# Power_Switch.net
KiCad netlist of a schematic drawn in Altium Designer
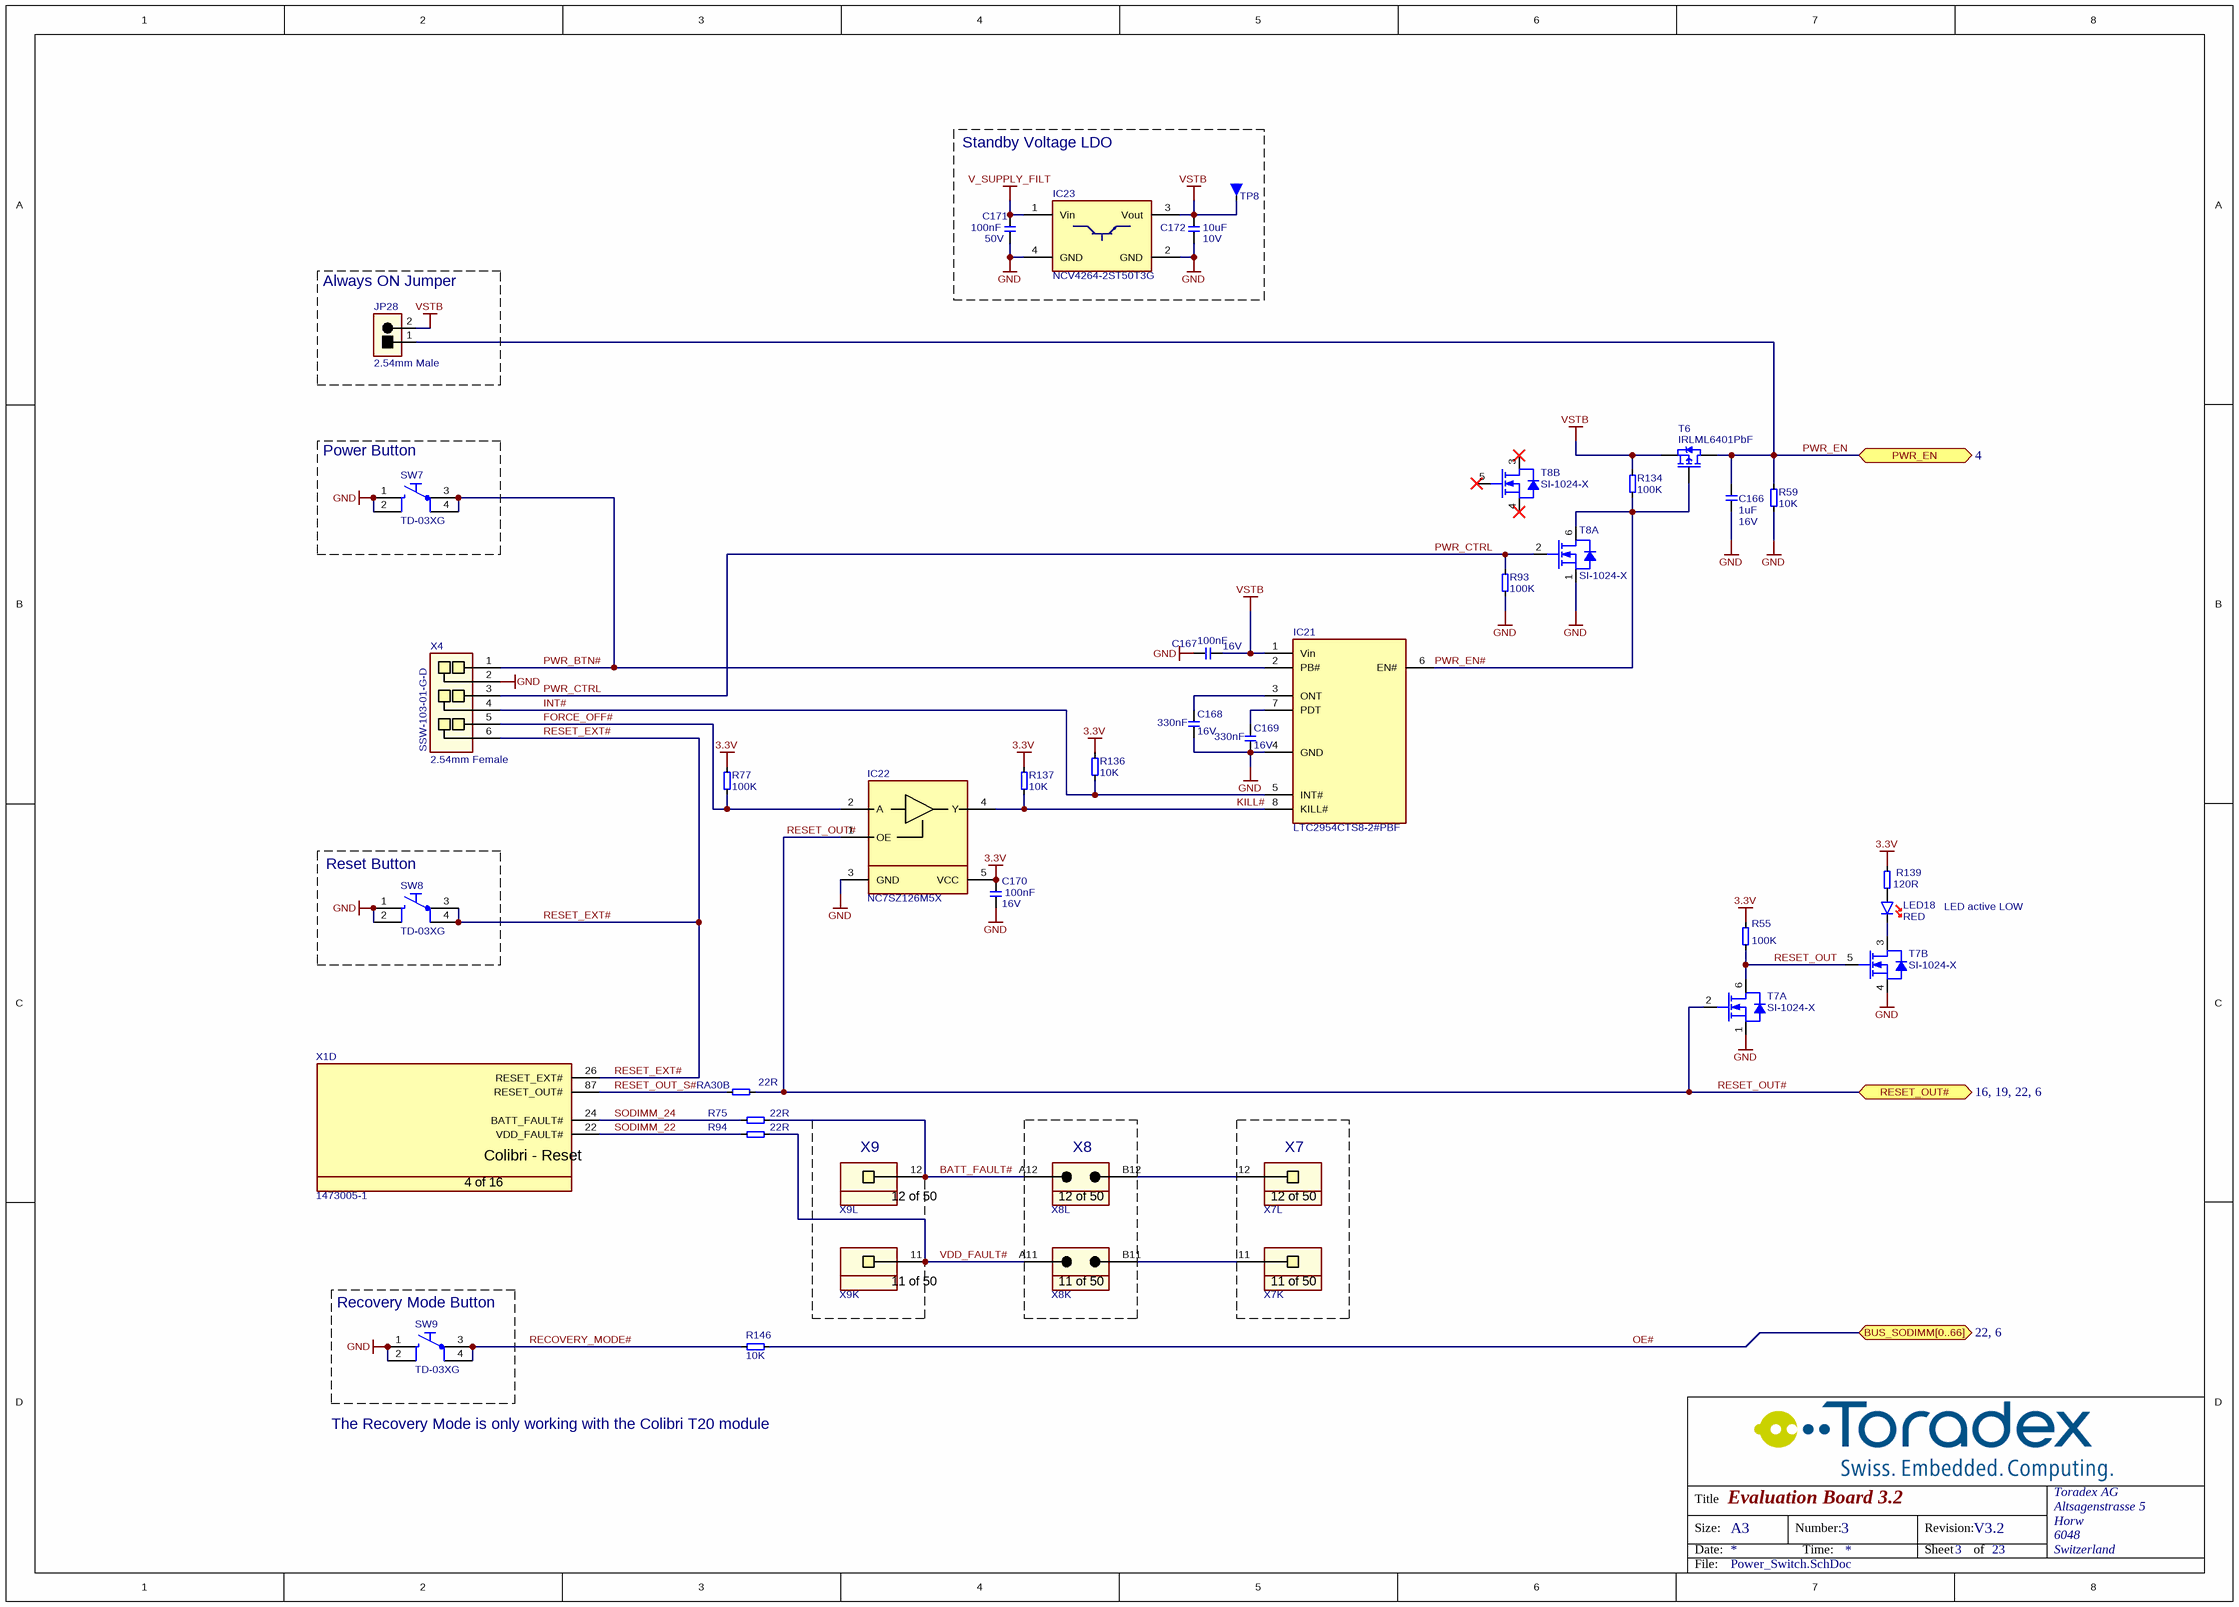
[diagram p0: Power_Switch.SchDoc]

(export (version "E")
  (design (tool "Eeschema 10.0.6"))
  (components
    (comp (ref "C166")
      (value "1uF")
      (footprint "T_CAPC0603X33N")
      (description "Capacitor Ceramic X5R 1uF 16V 20% 0603")
      (fields (field (name "TOLERANCE") "20%") (field (name "RATING") "16V"))
      (libsource (lib "Evaluation Board") (part "C-X5R-1uF-16V-20%-0603"))
    )
    (comp (ref "C167")
      (value "100nF")
      (footprint "T_CAPC0603X33N")
      (description "Capacitor Ceramic X7R 100nF 16V 10% 0603")
      (fields (field (name "TOLERANCE") "10%") (field (name "RATING") "16V"))
      (libsource (lib "Evaluation Board") (part "C-X7R-100nF-16V-10%-0603"))
    )
    (comp (ref "C168")
      (value "330nF")
      (footprint "T_CAPC0805X125N")
      (description "Capacitor Ceramic X7R 330nF 16V 10% 0805")
      (fields (field (name "TOLERANCE") "10%") (field (name "RATING") "16V"))
      (libsource (lib "Evaluation Board") (part "C-X7R-330nF-16V-10%-0805"))
    )
    (comp (ref "C169")
      (value "330nF")
      (footprint "T_CAPC0805X125N")
      (description "Capacitor Ceramic X7R 330nF 16V 10% 0805")
      (fields (field (name "TOLERANCE") "10%") (field (name "RATING") "16V"))
      (libsource (lib "Evaluation Board") (part "C-X7R-330nF-16V-10%-0805"))
    )
    (comp (ref "C170")
      (value "100nF")
      (footprint "T_CAPC0603X33N")
      (description "Capacitor Ceramic X7R 100nF 16V 10% 0603")
      (fields (field (name "TOLERANCE") "10%") (field (name "RATING") "16V"))
      (libsource (lib "Evaluation Board") (part "C-X7R-100nF-16V-10%-0603"))
    )
    (comp (ref "C171")
      (value "100nF")
      (footprint "T_CAPC0603X33N")
      (description "Capacitor Ceramic X7R 100nF 50V 20% 0603")
      (fields (field (name "TOLERANCE") "20%") (field (name "RATING") "50V"))
      (libsource (lib "Evaluation Board") (part "C-X7R-100nF-50V-20%-0603"))
    )
    (comp (ref "C172")
      (value "10uF")
      (footprint "T_CAPC0805X125N")
      (description "Capacitor Ceramic X5R 10uF 10V 20% 0805")
      (fields (field (name "TOLERANCE") "20%") (field (name "RATING") "10V"))
      (libsource (lib "Evaluation Board") (part "C-X5R-10uF-10V-20%-0805"))
    )
    (comp (ref "IC21")
      (value "LTC2954CTS8-2#PBF")
      (footprint "T_LINEAR_LTC2954CTS8-2#PBF")
      (description "Push Button On/Off Controller")
      (fields (field (name "MANUFACTURER PART NO.") "LTC2954CTS8-2#PBF"))
      (libsource (lib "Evaluation Board") (part "IC-LIN-LTC2954CTS8-2#PBF"))
    )
    (comp (ref "IC22")
      (value "NC7SZ126M5X")
      (footprint "SOT95P279X142-5N")
      (description "NC7SZ126M5X  Buffer Three-State Output")
      (fields (field (name "MANUFACTURER PART NO.") "NC7SZ126M5X"))
      (libsource (lib "Evaluation Board") (part "IC-FAR-NC7SZ126M5X"))
    )
    (comp (ref "IC23")
      (value "NCV4264-2ST50T3G")
      (footprint "T_ON_NCV4264-2ST50T3G")
      (description "NCV4264-2ST50T3G LDO Regulator")
      (fields (field (name "MANUFACTURER PART NO.") "NCV4264-2ST50T3G"))
      (libsource (lib "Evaluation Board") (part "IC-ON-NCV4264-2ST50T3G"))
    )
    (comp (ref "JP28")
      (value "TSW-101-07-G-D")
      (footprint "T_Samtec_TSW-101-07-G-D")
      (description "Header male, 1x2 Pins, 2.54 mm pitch")
      (libsource (lib "Evaluation Board") (part "CON-Samtec-TSW-101-07-G-D"))
    )
    (comp (ref "LED18")
      (value "LS T670-K1L2-1")
      (footprint "T_Osram_T670_RED")
      (description "LED red, Osram LS T670-K1L2-1")
      (fields (field (name "COLOR") "RED"))
      (libsource (lib "Evaluation Board") (part "LED-Osram-LS T670-K1L2-1"))
    )
    (comp (ref "R55")
      (value "100K")
      (footprint "T_RESC0603X30N")
      (description "Resistor 100 Kohm 63mW 5% 0603")
      (fields (field (name "TOLERANCE") "5%"))
      (libsource (lib "Evaluation Board") (part "R-100KR-63mW-5%-0603"))
    )
    (comp (ref "R59")
      (value "10K")
      (footprint "T_RESC0603X30N")
      (description "Resistor 10 Kohm 63mW 5% 0603")
      (fields (field (name "TOLERANCE") "5%"))
      (libsource (lib "Evaluation Board") (part "R-10KR-63mW-5%-0603"))
    )
    (comp (ref "R75")
      (value "22R")
      (footprint "RESC1005X40N")
      (description "Resistor 22 ohm 63mW 5% 0402")
      (fields (field (name "TOLERANCE") "5%"))
      (libsource (lib "Evaluation Board") (part "R-22R-63mW-5%-0402"))
    )
    (comp (ref "R77")
      (value "100K")
      (footprint "T_RESC0603X30N")
      (description "Resistor 100 Kohm 63mW 5% 0603")
      (fields (field (name "TOLERANCE") "5%"))
      (libsource (lib "Evaluation Board") (part "R-100KR-63mW-5%-0603"))
    )
    (comp (ref "R93")
      (value "100K")
      (footprint "T_RESC0603X30N")
      (description "Resistor 100 Kohm 63mW 5% 0603")
      (fields (field (name "TOLERANCE") "5%"))
      (libsource (lib "Evaluation Board") (part "R-100KR-63mW-5%-0603"))
    )
    (comp (ref "R94")
      (value "22R")
      (footprint "RESC1005X40N")
      (description "Resistor 22 ohm 63mW 5% 0402")
      (fields (field (name "TOLERANCE") "5%"))
      (libsource (lib "Evaluation Board") (part "R-22R-63mW-5%-0402"))
    )
    (comp (ref "R134")
      (value "100K")
      (footprint "T_RESC0603X30N")
      (description "Resistor 100 Kohm 63mW 5% 0603")
      (fields (field (name "TOLERANCE") "5%"))
      (libsource (lib "Evaluation Board") (part "R-100KR-63mW-5%-0603"))
    )
    (comp (ref "R136")
      (value "10K")
      (footprint "T_RESC0603X30N")
      (description "Resistor 10 Kohm 63mW 5% 0603")
      (fields (field (name "TOLERANCE") "5%"))
      (libsource (lib "Evaluation Board") (part "R-10KR-63mW-5%-0603"))
    )
    (comp (ref "R137")
      (value "10K")
      (footprint "T_RESC0603X30N")
      (description "Resistor 10 Kohm 63mW 5% 0603")
      (fields (field (name "TOLERANCE") "5%"))
      (libsource (lib "Evaluation Board") (part "R-10KR-63mW-5%-0603"))
    )
    (comp (ref "R139")
      (value "120R")
      (footprint "T_RESC0603X30N")
      (description "Resistor 120 ohm 63mW 5% 0603")
      (fields (field (name "TOLERANCE") "5%"))
      (libsource (lib "Evaluation Board") (part "R-120R-63mW-5%-0603"))
    )
    (comp (ref "R146")
      (value "10K")
      (footprint "T_RESC0603X30N")
      (description "Resistor 10 Kohm 63mW 5% 0603")
      (fields (field (name "TOLERANCE") "5%"))
      (libsource (lib "Evaluation Board") (part "R-10KR-63mW-5%-0603"))
    )
    (comp (ref "RA30")
      (value "22R")
      (footprint "T_Resistor_Array_X4")
      (description "Resistor Array 22 R 63mW 5% 1206")
      (fields (field (name "TOLERANCE") "5%"))
      (libsource (lib "Evaluation Board") (part "RA-22R-63mW-5%-1206-div"))
    )
    (comp (ref "SW7")
      (value "TD-03XG")
      (footprint "T_WMF_TD-03XG")
      (description "Switch")
      (libsource (lib "Evaluation Board") (part "SW-WMF-TD-03XG"))
    )
    (comp (ref "SW8")
      (value "TD-03XG")
      (footprint "T_WMF_TD-03XG")
      (description "Switch")
      (libsource (lib "Evaluation Board") (part "SW-WMF-TD-03XG"))
    )
    (comp (ref "SW9")
      (value "TD-03XG")
      (footprint "T_WMF_TD-03XG")
      (description "Switch")
      (libsource (lib "Evaluation Board") (part "SW-WMF-TD-03XG"))
    )
    (comp (ref "T6")
      (value "IRLML6401PbF")
      (footprint "SOT95P237X112-3N")
      (description "p-channel MOSFET, IRLML6401PbF")
      (libsource (lib "Evaluation Board") (part "T-IR-IRLML6401PbF-SOT-23"))
    )
    (comp (ref "T7")
      (value "T-Vishay-SI-1024X-N")
      (footprint "SOTFL50P160X60-6N")
      (description "Dual N-Channel 20V (D-S)  MOSFET")
      (fields (field (name "MANUFACTURER PART NO.") "SI-1024-X"))
      (libsource (lib "Evaluation Board") (part "T-Vishay-SI-1024X-N"))
    )
    (comp (ref "T8")
      (value "T-Vishay-SI-1024X-N")
      (footprint "SOTFL50P160X60-6N")
      (description "Dual N-Channel 20V (D-S)  MOSFET")
      (fields (field (name "MANUFACTURER PART NO.") "SI-1024-X"))
      (libsource (lib "Evaluation Board") (part "T-Vishay-SI-1024X-N"))
    )
    (comp (ref "TP8")
      (value "Testpin")
      (footprint "T_TP-THT")
      (description "Testpin TH")
      (libsource (lib "Evaluation Board") (part "Testpin"))
    )
    (comp (ref "X1")
      (value "CON-Tyco-1473005-1-200-0.6mm")
      (footprint "T_Tyco_1473005-1")
      (description "SODIMM Connector")
      (fields (field (name "MANUFACTURER PART NO.") "1473005-1"))
      (libsource (lib "Evaluation Board") (part "CON-Tyco-1473005-1-200-0.6mm"))
    )
    (comp (ref "X4")
      (value "TSW-103-01-G-D")
      (footprint "T_Samtec_SSW-103-01-G-D")
      (description "Header Female, 2x3 Pins, 2.54mm pitch")
      (fields (field (name "MANUFACTURER PART NO.") "SSW-103-01-G-D"))
      (libsource (lib "Evaluation Board") (part "CON-Samtec-SSW-103-01-G-D"))
    )
    (comp (ref "X7")
      (value "SSW-110-01-G-S")
      (footprint "T_Samtec_SSW-110-01-G-S")
      (description "Header 1x50 pin 2.54mm pitch")
      (libsource (lib "Evaluation Board") (part "CON-Samtec-SSW-110-01-G-S"))
    )
    (comp (ref "X8")
      (value "TSW-110-07-G-D")
      (footprint "T_Samtec_TSW-110-07-G-D")
      (description "Header 2x50 pin 2.54mm pitch")
      (libsource (lib "Evaluation Board") (part "CON-Samtec-TSW-110-07-G-D"))
    )
    (comp (ref "X9")
      (value "SSW-110-01-G-S")
      (footprint "T_Samtec_SSW-110-01-G-S")
      (description "Header 1x50 pin 2.54mm pitch")
      (libsource (lib "") (part "CON-Samtec-SSW-110-01-G-S_1"))
    )
  )
  (nets
    (net (code "68") (name "/BATT_FAULT#") (class "Default")
      (node (ref "R75") (pin "2") (pinfunction "2_2") (pintype "passive"))
      (node (ref "X8") (pin "A12") (pinfunction "A12_A12") (pintype "passive"))
      (node (ref "X9") (pin "12") (pinfunction "12_12") (pintype "passive"))
    )
    (net (code "70") (name "/FORCE_OFF#") (class "Default")
      (node (ref "IC22") (pin "2") (pinfunction "A_2") (pintype "passive"))
      (node (ref "R77") (pin "1") (pinfunction "1_1") (pintype "passive"))
      (node (ref "X4") (pin "5") (pinfunction "5_5") (pintype "passive"))
    )
    (net (code "71") (name "/INT#") (class "Default")
      (node (ref "IC21") (pin "5") (pinfunction "INT#_5") (pintype "passive"))
      (node (ref "R136") (pin "2") (pinfunction "2_2") (pintype "passive"))
      (node (ref "X4") (pin "4") (pinfunction "4_4") (pintype "passive"))
    )
    (net (code "72") (name "/KILL#") (class "Default")
      (node (ref "IC21") (pin "8") (pinfunction "KILL#_8") (pintype "passive"))
      (node (ref "IC22") (pin "4") (pinfunction "Y_4") (pintype "passive"))
      (node (ref "R137") (pin "2") (pinfunction "2_2") (pintype "passive"))
    )
    (net (code "73") (name "/OE#") (class "Default")
      (node (ref "R146") (pin "2") (pinfunction "2_2") (pintype "passive"))
    )
    (net (code "74") (name "/PWR_BTN#") (class "Default")
      (node (ref "IC21") (pin "2") (pinfunction "PB#_2") (pintype "passive"))
      (node (ref "SW7") (pin "3") (pinfunction "3_3") (pintype "passive"))
      (node (ref "SW7") (pin "4") (pinfunction "4_4") (pintype "passive"))
      (node (ref "X4") (pin "1") (pinfunction "1_1") (pintype "passive"))
    )
    (net (code "75") (name "/PWR_CTRL") (class "Default")
      (node (ref "R93") (pin "2") (pinfunction "2_2") (pintype "passive"))
      (node (ref "T8") (pin "2") (pinfunction "G_2") (pintype "passive"))
      (node (ref "X4") (pin "3") (pinfunction "3_3") (pintype "passive"))
    )
    (net (code "76") (name "/PWR_EN") (class "Default")
      (node (ref "C166") (pin "2") (pinfunction "2_2") (pintype "passive"))
      (node (ref "JP28") (pin "1") (pinfunction "1_1") (pintype "passive"))
      (node (ref "R59") (pin "2") (pinfunction "2_2") (pintype "passive"))
      (node (ref "T6") (pin "3") (pinfunction "3_3") (pintype "passive"))
    )
    (net (code "77") (name "/PWR_EN#") (class "Default")
      (node (ref "IC21") (pin "6") (pinfunction "EN#_6") (pintype "passive"))
      (node (ref "R134") (pin "1") (pinfunction "1_1") (pintype "passive"))
      (node (ref "T6") (pin "1") (pinfunction "1_1") (pintype "passive"))
      (node (ref "T8") (pin "6") (pinfunction "D_6") (pintype "passive"))
    )
    (net (code "78") (name "/RECOVERY_MODE#") (class "Default")
      (node (ref "R146") (pin "1") (pinfunction "1_1") (pintype "passive"))
      (node (ref "SW9") (pin "3") (pinfunction "3_3") (pintype "passive"))
      (node (ref "SW9") (pin "4") (pinfunction "4_4") (pintype "passive"))
    )
    (net (code "79") (name "/RESET_EXT#") (class "Default")
      (node (ref "SW8") (pin "3") (pinfunction "3_3") (pintype "passive"))
      (node (ref "SW8") (pin "4") (pinfunction "4_4") (pintype "passive"))
      (node (ref "X1") (pin "26") (pinfunction "RESET_EXT#_26") (pintype "passive"))
      (node (ref "X4") (pin "6") (pinfunction "6_6") (pintype "passive"))
    )
    (net (code "80") (name "/RESET_OUT") (class "Default")
      (node (ref "R55") (pin "1") (pinfunction "1_1") (pintype "passive"))
      (node (ref "T7") (pin "5") (pinfunction "G_5") (pintype "passive"))
      (node (ref "T7") (pin "6") (pinfunction "D_6") (pintype "passive"))
    )
    (net (code "81") (name "/RESET_OUT#") (class "Default")
      (node (ref "IC22") (pin "1") (pinfunction "OE_1") (pintype "passive"))
      (node (ref "RA30") (pin "6") (pinfunction "6_6") (pintype "passive"))
      (node (ref "T7") (pin "2") (pinfunction "G_2") (pintype "passive"))
    )
    (net (code "82") (name "/RESET_OUT_S#") (class "Default")
      (node (ref "RA30") (pin "2") (pinfunction "2_2") (pintype "passive"))
      (node (ref "X1") (pin "87") (pinfunction "RESET_OUT#_87") (pintype "passive"))
    )
    (net (code "83") (name "/SODIMM_22") (class "Default")
      (node (ref "R94") (pin "1") (pinfunction "1_1") (pintype "passive"))
      (node (ref "X1") (pin "22") (pinfunction "VDD_FAULT#_22") (pintype "passive"))
    )
    (net (code "84") (name "/SODIMM_24") (class "Default")
      (node (ref "R75") (pin "1") (pinfunction "1_1") (pintype "passive"))
      (node (ref "X1") (pin "24") (pinfunction "BATT_FAULT#_24") (pintype "passive"))
    )
    (net (code "85") (name "/VDD_FAULT#") (class "Default")
      (node (ref "R94") (pin "2") (pinfunction "2_2") (pintype "passive"))
      (node (ref "X8") (pin "A11") (pinfunction "A11_A11") (pintype "passive"))
      (node (ref "X9") (pin "11") (pinfunction "11_11") (pintype "passive"))
    )
    (net (code "86") (name "3.3V") (class "Default")
      (node (ref "C170") (pin "1") (pinfunction "1_1") (pintype "passive"))
      (node (ref "IC22") (pin "5") (pinfunction "VCC_5") (pintype "passive"))
      (node (ref "R136") (pin "1") (pinfunction "1_1") (pintype "passive"))
      (node (ref "R137") (pin "1") (pinfunction "1_1") (pintype "passive"))
      (node (ref "R139") (pin "2") (pinfunction "2_2") (pintype "passive"))
      (node (ref "R55") (pin "2") (pinfunction "2_2") (pintype "passive"))
      (node (ref "R77") (pin "2") (pinfunction "2_2") (pintype "passive"))
    )
    (net (code "87") (name "GND") (class "Default")
      (node (ref "C166") (pin "1") (pinfunction "1_1") (pintype "passive"))
      (node (ref "C167") (pin "1") (pinfunction "1_1") (pintype "passive"))
      (node (ref "C168") (pin "1") (pinfunction "1_1") (pintype "passive"))
      (node (ref "C169") (pin "1") (pinfunction "1_1") (pintype "passive"))
      (node (ref "C170") (pin "2") (pinfunction "2_2") (pintype "passive"))
      (node (ref "C171") (pin "1") (pinfunction "1_1") (pintype "passive"))
      (node (ref "C172") (pin "1") (pinfunction "1_1") (pintype "passive"))
      (node (ref "IC21") (pin "4") (pinfunction "GND_4") (pintype "passive"))
      (node (ref "IC22") (pin "3") (pinfunction "GND_3") (pintype "passive"))
      (node (ref "IC23") (pin "2") (pinfunction "GND_2") (pintype "passive"))
      (node (ref "IC23") (pin "4") (pinfunction "GND_4") (pintype "passive"))
      (node (ref "R59") (pin "1") (pinfunction "1_1") (pintype "passive"))
      (node (ref "R93") (pin "1") (pinfunction "1_1") (pintype "passive"))
      (node (ref "SW7") (pin "1") (pinfunction "1_1") (pintype "passive"))
      (node (ref "SW7") (pin "2") (pinfunction "2_2") (pintype "passive"))
      (node (ref "SW8") (pin "1") (pinfunction "1_1") (pintype "passive"))
      (node (ref "SW8") (pin "2") (pinfunction "2_2") (pintype "passive"))
      (node (ref "SW9") (pin "1") (pinfunction "1_1") (pintype "passive"))
      (node (ref "SW9") (pin "2") (pinfunction "2_2") (pintype "passive"))
      (node (ref "T7") (pin "1") (pinfunction "S_1") (pintype "passive"))
      (node (ref "T7") (pin "4") (pinfunction "S_4") (pintype "passive"))
      (node (ref "T8") (pin "1") (pinfunction "S_1") (pintype "passive"))
      (node (ref "X4") (pin "2") (pinfunction "2_2") (pintype "passive"))
    )
    (net (code "88") (name "Net-(IC21-ONT)") (class "Default")
      (node (ref "C168") (pin "2") (pinfunction "2_2") (pintype "passive"))
      (node (ref "IC21") (pin "3") (pinfunction "ONT_3") (pintype "passive"))
    )
    (net (code "89") (name "Net-(IC21-PDT)") (class "Default")
      (node (ref "C169") (pin "2") (pinfunction "2_2") (pintype "passive"))
      (node (ref "IC21") (pin "7") (pinfunction "PDT_7") (pintype "passive"))
    )
    (net (code "90") (name "Net-(LED18-PadA)") (class "Default")
      (node (ref "LED18") (pin "A") (pinfunction "A_A") (pintype "passive"))
      (node (ref "R139") (pin "1") (pinfunction "1_1") (pintype "passive"))
    )
    (net (code "91") (name "Net-(T7B-D)") (class "Default")
      (node (ref "LED18") (pin "K") (pinfunction "K_K") (pintype "passive"))
      (node (ref "T7") (pin "3") (pinfunction "D_3") (pintype "passive"))
    )
    (net (code "92") (name "Net-(X7-Pad11)") (class "Default")
      (node (ref "X7") (pin "11") (pinfunction "11_11") (pintype "passive"))
      (node (ref "X8") (pin "B11") (pinfunction "B11_B11") (pintype "passive"))
    )
    (net (code "93") (name "Net-(X7-Pad12)") (class "Default")
      (node (ref "X7") (pin "12") (pinfunction "12_12") (pintype "passive"))
      (node (ref "X8") (pin "B12") (pinfunction "B12_B12") (pintype "passive"))
    )
    (net (code "94") (name "VSTB") (class "Default")
      (node (ref "C167") (pin "2") (pinfunction "2_2") (pintype "passive"))
      (node (ref "C172") (pin "2") (pinfunction "2_2") (pintype "passive"))
      (node (ref "IC21") (pin "1") (pinfunction "Vin_1") (pintype "passive"))
      (node (ref "IC23") (pin "3") (pinfunction "Vout_3") (pintype "passive"))
      (node (ref "JP28") (pin "2") (pinfunction "2_2") (pintype "passive"))
      (node (ref "R134") (pin "2") (pinfunction "2_2") (pintype "passive"))
      (node (ref "T6") (pin "2") (pinfunction "2_2") (pintype "passive"))
      (node (ref "TP8") (pin "1") (pinfunction "1_1") (pintype "passive"))
    )
    (net (code "95") (name "V_SUPPLY_FILT") (class "Default")
      (node (ref "C171") (pin "2") (pinfunction "2_2") (pintype "passive"))
      (node (ref "IC23") (pin "1") (pinfunction "Vin_1") (pintype "passive"))
    )
    (net (code "96") (name "unconnected-(T8B-D-Pad3)") (class "Default")
      (node (ref "T8") (pin "3") (pinfunction "D_3") (pintype "passive+no_connect"))
    )
    (net (code "97") (name "unconnected-(T8B-G-Pad5)") (class "Default")
      (node (ref "T8") (pin "5") (pinfunction "G_5") (pintype "passive+no_connect"))
    )
    (net (code "98") (name "unconnected-(T8B-S-Pad4)") (class "Default")
      (node (ref "T8") (pin "4") (pinfunction "S_4") (pintype "passive+no_connect"))
    )
  )
)
